# Project.net
KiCad netlist of a schematic drawn in EasyEDA Pro
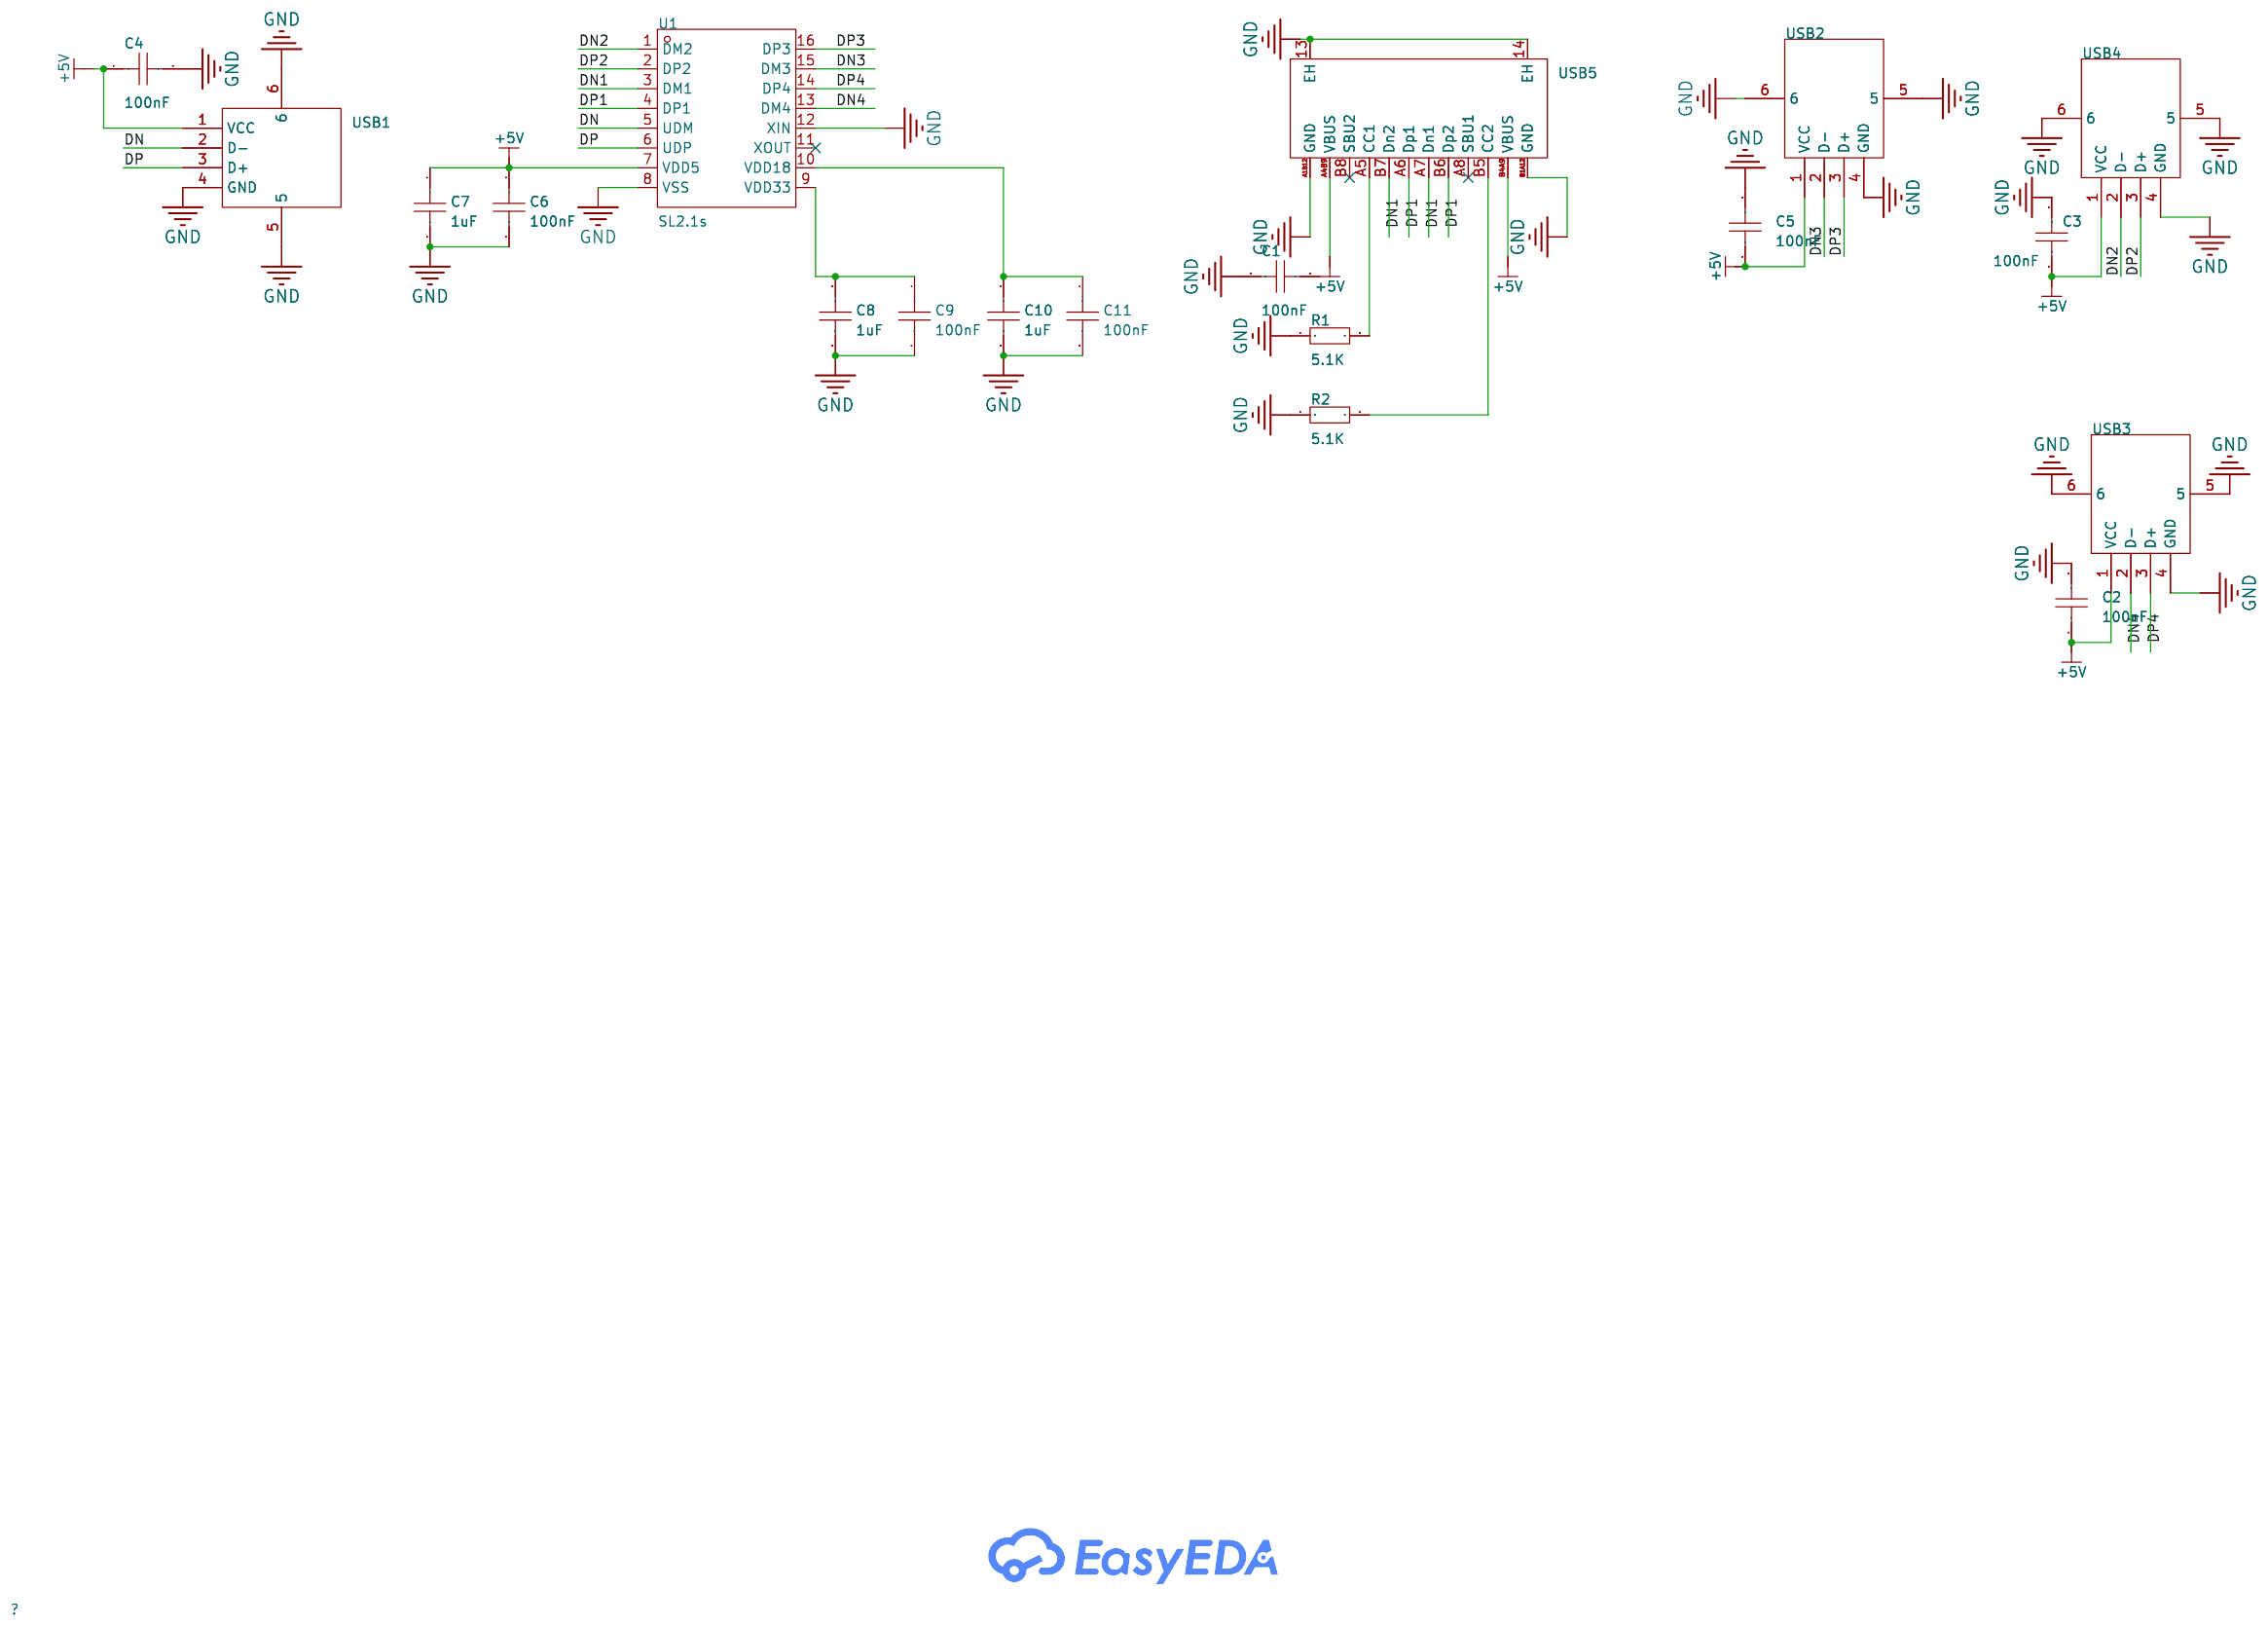
[diagram p0: schematic sheet]

(export (version "E")
  (design (tool "Eeschema 10.0.6"))
  (components
    (comp (ref "C1")
      (value "100nF")
      (footprint "easyedapro:C0603")
      (libsource (lib "easyedapro") (part "CAP"))
    )
    (comp (ref "C2")
      (value "100nF")
      (footprint "easyedapro:C0603")
      (libsource (lib "easyedapro") (part "CAP"))
    )
    (comp (ref "C3")
      (value "100nF")
      (footprint "easyedapro:C0603")
      (libsource (lib "easyedapro") (part "CAP"))
    )
    (comp (ref "C4")
      (value "100nF")
      (footprint "easyedapro:C0603")
      (libsource (lib "easyedapro") (part "CAP"))
    )
    (comp (ref "C5")
      (value "100nF")
      (footprint "easyedapro:C0603")
      (libsource (lib "easyedapro") (part "CAP"))
    )
    (comp (ref "C6")
      (value "100nF")
      (footprint "easyedapro:C0603")
      (libsource (lib "easyedapro") (part "CAP"))
    )
    (comp (ref "C7") (value "1uF") (footprint "easyedapro:C0603") (libsource (lib "easyedapro") (part "CAP")))
    (comp (ref "C8") (value "1uF") (footprint "easyedapro:C0603") (libsource (lib "easyedapro") (part "CAP")))
    (comp (ref "C9")
      (value "100nF")
      (footprint "easyedapro:C0603")
      (libsource (lib "easyedapro") (part "CAP"))
    )
    (comp (ref "C10")
      (value "1uF")
      (footprint "easyedapro:C0603")
      (libsource (lib "easyedapro") (part "CAP"))
    )
    (comp (ref "C11")
      (value "100nF")
      (footprint "easyedapro:C0603")
      (libsource (lib "easyedapro") (part "CAP"))
    )
    (comp (ref "R1")
      (value "5.1K")
      (footprint "easyedapro:R0603")
      (libsource (lib "easyedapro") (part "Res"))
    )
    (comp (ref "R2")
      (value "5.1K")
      (footprint "easyedapro:R0603")
      (libsource (lib "easyedapro") (part "Res"))
    )
    (comp (ref "U1")
      (value "SL2.1s")
      (footprint "easyedapro:SSOP-16_L4.6-W2.6-P0.53-LS4.0-BL")
      (fields (field (name "Manufacturer") "CoreChips(和芯润德)"))
      (libsource (lib "easyedapro") (part "SL2.1S"))
    )
    (comp (ref "USB1")
      (value "10.0 QHHTZB6.3")
      (footprint "easyedapro:USB-A-TH_10.0QHHTZB6.3")
      (fields (field (name "Manufacturer") "SHOU HAN(首韩)"))
      (libsource (lib "easyedapro") (part "10.0 QHHTZB6.3"))
    )
    (comp (ref "USB2")
      (value "10.0 QHHTZB6.3")
      (footprint "easyedapro:USB-A-TH_10.0QHHTZB6.3")
      (fields (field (name "Manufacturer") "SHOU HAN(首韩)"))
      (libsource (lib "easyedapro") (part "10.0 QHHTZB6.3"))
    )
    (comp (ref "USB3")
      (value "10.0 QHHTZB6.3")
      (footprint "easyedapro:USB-A-TH_10.0QHHTZB6.3")
      (fields (field (name "Manufacturer") "SHOU HAN(首韩)"))
      (libsource (lib "easyedapro") (part "10.0 QHHTZB6.3"))
    )
    (comp (ref "USB4")
      (value "10.0 QHHTZB6.3")
      (footprint "easyedapro:USB-A-TH_10.0QHHTZB6.3")
      (fields (field (name "Manufacturer") "SHOU HAN(首韩)"))
      (libsource (lib "easyedapro") (part "10.0 QHHTZB6.3"))
    )
    (comp (ref "USB5")
      (value "TYPE-C 16PIN 2MD(073)")
      (footprint "easyedapro:USB-C-SMD_TYPE-C-16PIN-2MD-073")
      (fields (field (name "Manufacturer") "SHOU HAN(首韩)"))
      (libsource (lib "easyedapro") (part "TYPE-C 16PIN 2MD(073)"))
    )
  )
  (nets
    (net (code "1") (name "+5V") (class "Default")
      (node (ref "C2") (pin "1") (pinfunction "1_1") (pintype "input"))
      (node (ref "C3") (pin "2") (pinfunction "2_2") (pintype "input"))
      (node (ref "C4") (pin "1") (pinfunction "1_1") (pintype "input"))
      (node (ref "C5") (pin "2") (pinfunction "2_2") (pintype "input"))
      (node (ref "C6") (pin "1") (pinfunction "1_1") (pintype "input"))
      (node (ref "C7") (pin "1") (pinfunction "1_1") (pintype "input"))
      (node (ref "U1") (pin "7") (pinfunction "VDD5_7") (pintype "unspecified"))
      (node (ref "USB1") (pin "1") (pinfunction "VCC_1") (pintype "unspecified"))
      (node (ref "USB2") (pin "1") (pinfunction "VCC_1") (pintype "unspecified"))
      (node (ref "USB3") (pin "1") (pinfunction "VCC_1") (pintype "unspecified"))
      (node (ref "USB4") (pin "1") (pinfunction "VCC_1") (pintype "unspecified"))
      (node (ref "USB5") (pin "A4B9") (pinfunction "VBUS_A4B9") (pintype "unspecified"))
      (node (ref "USB5") (pin "B4A9") (pinfunction "VBUS_B4A9") (pintype "unspecified"))
    )
    (net (code "2") (name "/DN") (class "Default")
      (node (ref "U1") (pin "5") (pinfunction "UDM_5") (pintype "unspecified"))
      (node (ref "USB1") (pin "2") (pinfunction "D-_2") (pintype "unspecified"))
    )
    (net (code "3") (name "/DN1") (class "Default")
      (node (ref "U1") (pin "3") (pinfunction "DM1_3") (pintype "unspecified"))
      (node (ref "USB5") (pin "A7") (pinfunction "Dn1_A7") (pintype "unspecified"))
      (node (ref "USB5") (pin "B7") (pinfunction "Dn2_B7") (pintype "unspecified"))
    )
    (net (code "4") (name "/DN2") (class "Default")
      (node (ref "U1") (pin "1") (pinfunction "DM2_1") (pintype "unspecified"))
      (node (ref "USB4") (pin "2") (pinfunction "D-_2") (pintype "unspecified"))
    )
    (net (code "5") (name "/DN3") (class "Default")
      (node (ref "U1") (pin "15") (pinfunction "DM3_15") (pintype "unspecified"))
      (node (ref "USB2") (pin "2") (pinfunction "D-_2") (pintype "unspecified"))
    )
    (net (code "6") (name "/DN4") (class "Default")
      (node (ref "U1") (pin "13") (pinfunction "DM4_13") (pintype "unspecified"))
      (node (ref "USB3") (pin "2") (pinfunction "D-_2") (pintype "unspecified"))
    )
    (net (code "7") (name "/DP") (class "Default")
      (node (ref "U1") (pin "6") (pinfunction "UDP_6") (pintype "unspecified"))
      (node (ref "USB1") (pin "3") (pinfunction "D+_3") (pintype "unspecified"))
    )
    (net (code "8") (name "/DP1") (class "Default")
      (node (ref "U1") (pin "4") (pinfunction "DP1_4") (pintype "unspecified"))
      (node (ref "USB5") (pin "A6") (pinfunction "Dp1_A6") (pintype "unspecified"))
      (node (ref "USB5") (pin "B6") (pinfunction "Dp2_B6") (pintype "unspecified"))
    )
    (net (code "9") (name "/DP2") (class "Default")
      (node (ref "U1") (pin "2") (pinfunction "DP2_2") (pintype "unspecified"))
      (node (ref "USB4") (pin "3") (pinfunction "D+_3") (pintype "unspecified"))
    )
    (net (code "10") (name "/DP3") (class "Default")
      (node (ref "U1") (pin "16") (pinfunction "DP3_16") (pintype "unspecified"))
      (node (ref "USB2") (pin "3") (pinfunction "D+_3") (pintype "unspecified"))
    )
    (net (code "11") (name "/DP4") (class "Default")
      (node (ref "U1") (pin "14") (pinfunction "DP4_14") (pintype "unspecified"))
      (node (ref "USB3") (pin "3") (pinfunction "D+_3") (pintype "unspecified"))
    )
    (net (code "12") (name "GND") (class "Default")
      (node (ref "C1") (pin "2") (pinfunction "2_2") (pintype "input"))
      (node (ref "C10") (pin "2") (pinfunction "2_2") (pintype "input"))
      (node (ref "C11") (pin "2") (pinfunction "2_2") (pintype "input"))
      (node (ref "C2") (pin "2") (pinfunction "2_2") (pintype "input"))
      (node (ref "C3") (pin "1") (pinfunction "1_1") (pintype "input"))
      (node (ref "C4") (pin "2") (pinfunction "2_2") (pintype "input"))
      (node (ref "C5") (pin "1") (pinfunction "1_1") (pintype "input"))
      (node (ref "C6") (pin "2") (pinfunction "2_2") (pintype "input"))
      (node (ref "C7") (pin "2") (pinfunction "2_2") (pintype "input"))
      (node (ref "C8") (pin "2") (pinfunction "2_2") (pintype "input"))
      (node (ref "C9") (pin "2") (pinfunction "2_2") (pintype "input"))
      (node (ref "R1") (pin "1") (pinfunction "1_1") (pintype "input"))
      (node (ref "R2") (pin "1") (pinfunction "1_1") (pintype "input"))
      (node (ref "U1") (pin "12") (pinfunction "XIN_12") (pintype "unspecified"))
      (node (ref "U1") (pin "8") (pinfunction "VSS_8") (pintype "unspecified"))
      (node (ref "USB1") (pin "4") (pinfunction "GND_4") (pintype "unspecified"))
      (node (ref "USB1") (pin "5") (pinfunction "5_5") (pintype "unspecified"))
      (node (ref "USB1") (pin "6") (pinfunction "6_6") (pintype "unspecified"))
      (node (ref "USB2") (pin "4") (pinfunction "GND_4") (pintype "unspecified"))
      (node (ref "USB2") (pin "5") (pinfunction "5_5") (pintype "unspecified"))
      (node (ref "USB2") (pin "6") (pinfunction "6_6") (pintype "unspecified"))
      (node (ref "USB3") (pin "4") (pinfunction "GND_4") (pintype "unspecified"))
      (node (ref "USB3") (pin "5") (pinfunction "5_5") (pintype "unspecified"))
      (node (ref "USB3") (pin "6") (pinfunction "6_6") (pintype "unspecified"))
      (node (ref "USB4") (pin "4") (pinfunction "GND_4") (pintype "unspecified"))
      (node (ref "USB4") (pin "5") (pinfunction "5_5") (pintype "unspecified"))
      (node (ref "USB4") (pin "6") (pinfunction "6_6") (pintype "unspecified"))
      (node (ref "USB5") (pin "13") (pinfunction "EH_13") (pintype "unspecified"))
      (node (ref "USB5") (pin "14") (pinfunction "EH_14") (pintype "unspecified"))
      (node (ref "USB5") (pin "A1B12") (pinfunction "GND_A1B12") (pintype "unspecified"))
      (node (ref "USB5") (pin "B1A12") (pinfunction "GND_B1A12") (pintype "unspecified"))
    )
    (net (code "13") (name "Net-(U1-VDD18)") (class "Default")
      (node (ref "C10") (pin "1") (pinfunction "1_1") (pintype "input"))
      (node (ref "C11") (pin "1") (pinfunction "1_1") (pintype "input"))
      (node (ref "U1") (pin "10") (pinfunction "VDD18_10") (pintype "unspecified"))
    )
    (net (code "14") (name "Net-(U1-VDD33)") (class "Default")
      (node (ref "C8") (pin "1") (pinfunction "1_1") (pintype "input"))
      (node (ref "C9") (pin "1") (pinfunction "1_1") (pintype "input"))
      (node (ref "U1") (pin "9") (pinfunction "VDD33_9") (pintype "unspecified"))
    )
    (net (code "15") (name "Net-(USB5-CC1)") (class "Default")
      (node (ref "R1") (pin "2") (pinfunction "2_2") (pintype "input"))
      (node (ref "USB5") (pin "A5") (pinfunction "CC1_A5") (pintype "unspecified"))
    )
    (net (code "16") (name "Net-(USB5-CC2)") (class "Default")
      (node (ref "R2") (pin "2") (pinfunction "2_2") (pintype "input"))
      (node (ref "USB5") (pin "B5") (pinfunction "CC2_B5") (pintype "unspecified"))
    )
    (net (code "17") (name "unconnected-(C1-Pad1)") (class "Default")
      (node (ref "C1") (pin "1") (pinfunction "1_1") (pintype "input"))
    )
    (net (code "18") (name "unconnected-(U1-XOUT-Pad11)") (class "Default")
      (node (ref "U1") (pin "11") (pinfunction "XOUT_11") (pintype "unspecified+no_connect"))
    )
    (net (code "19") (name "unconnected-(USB5-SBU1-PadA8)") (class "Default")
      (node (ref "USB5") (pin "A8") (pinfunction "SBU1_A8") (pintype "unspecified+no_connect"))
    )
    (net (code "20") (name "unconnected-(USB5-SBU2-PadB8)") (class "Default")
      (node (ref "USB5") (pin "B8") (pinfunction "SBU2_B8") (pintype "unspecified+no_connect"))
    )
  )
)
